# PCB-JOY-4AXIS_adaptorHirose.net
KiCad netlist of a schematic drawn in EAGLE
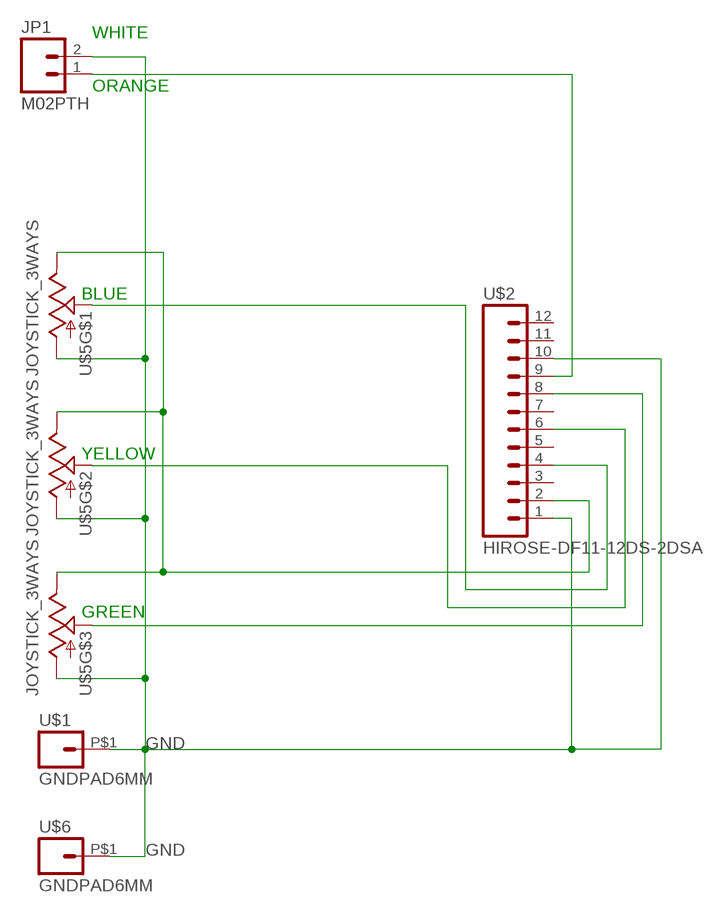
[diagram p0: schematic, sheet 1]

(export (version "E")
  (design (tool "Eeschema 10.0.6"))
  (components
    (comp (ref "JP1")
      (value "M02PTH")
      (footprint "eagle-import:1X02")
      (libsource (lib "eagle-import") (part "M02PTH"))
    )
    (comp (ref "U$1")
      (value "GNDPAD6MM")
      (footprint "eagle-import:3.2MMPAD6MM")
      (libsource (lib "eagle-import") (part "GNDPAD6MM"))
    )
    (comp (ref "U$2")
      (value "HIROSE-DF11-12DS-2DSA")
      (footprint "eagle-import:2X6HIROSE_DF11-12DS-2DSA")
      (libsource (lib "eagle-import") (part "HIROSE-DF11-12DS-2DSA"))
    )
    (comp (ref "U$5")
      (value "JOYSTICK_3WAYS")
      (footprint "eagle-import:JOYSTICK")
      (libsource (lib "eagle-import") (part "JOYSTICK_3WAYS"))
    )
    (comp (ref "U$6")
      (value "GNDPAD6MM")
      (footprint "eagle-import:3.2MMPAD6MM")
      (libsource (lib "eagle-import") (part "GNDPAD6MM"))
    )
  )
  (nets
    (net (code "1") (name "/GND") (class "Default")
      (node (ref "JP1") (pin "2") (pinfunction "2_2") (pintype "passive"))
      (node (ref "U$1") (pin "P$1") (pinfunction "1_P$1") (pintype "passive"))
      (node (ref "U$2") (pin "1") (pinfunction "1_1") (pintype "passive"))
      (node (ref "U$2") (pin "10") (pinfunction "10_10") (pintype "passive"))
      (node (ref "U$5") (pin "LR_COM") (pinfunction "A_LR_COM") (pintype "passive"))
      (node (ref "U$5") (pin "ROT_COM") (pinfunction "A_ROT_COM") (pintype "passive"))
      (node (ref "U$5") (pin "UD_COM") (pinfunction "A_UD_COM") (pintype "passive"))
      (node (ref "U$6") (pin "P$1") (pinfunction "1_P$1") (pintype "passive"))
    )
    (net (code "2") (name "Net-(JP1-Pad1)") (class "Default")
      (node (ref "JP1") (pin "1") (pinfunction "1_1") (pintype "passive"))
      (node (ref "U$2") (pin "9") (pinfunction "9_9") (pintype "passive"))
    )
    (net (code "3") (name "Net-(U$5A-E)") (class "Default")
      (node (ref "U$2") (pin "2") (pinfunction "2_2") (pintype "passive"))
      (node (ref "U$5") (pin "LR_V") (pinfunction "E_LR_V") (pintype "passive"))
      (node (ref "U$5") (pin "ROT_V") (pinfunction "E_ROT_V") (pintype "passive"))
      (node (ref "U$5") (pin "UD_V") (pinfunction "E_UD_V") (pintype "passive"))
    )
    (net (code "4") (name "Net-(U$5A-S)") (class "Default")
      (node (ref "U$2") (pin "4") (pinfunction "4_4") (pintype "passive"))
      (node (ref "U$5") (pin "LR_C") (pinfunction "S_LR_C") (pintype "passive"))
    )
    (net (code "5") (name "Net-(U$5B-S)") (class "Default")
      (node (ref "U$2") (pin "6") (pinfunction "6_6") (pintype "passive"))
      (node (ref "U$5") (pin "UD_C") (pinfunction "S_UD_C") (pintype "passive"))
    )
    (net (code "6") (name "Net-(U$5C-S)") (class "Default")
      (node (ref "U$2") (pin "8") (pinfunction "8_8") (pintype "passive"))
      (node (ref "U$5") (pin "ROT_C") (pinfunction "S_ROT_C") (pintype "passive"))
    )
    (net (code "7") (name "unconnected-(U$2-Pad3)") (class "Default")
      (node (ref "U$2") (pin "3") (pinfunction "3_3") (pintype "passive"))
    )
    (net (code "8") (name "unconnected-(U$2-Pad5)") (class "Default")
      (node (ref "U$2") (pin "5") (pinfunction "5_5") (pintype "passive"))
    )
    (net (code "9") (name "unconnected-(U$2-Pad7)") (class "Default")
      (node (ref "U$2") (pin "7") (pinfunction "7_7") (pintype "passive"))
    )
    (net (code "10") (name "unconnected-(U$2-Pad11)") (class "Default")
      (node (ref "U$2") (pin "11") (pinfunction "11_11") (pintype "passive"))
    )
    (net (code "11") (name "unconnected-(U$2-Pad12)") (class "Default")
      (node (ref "U$2") (pin "12") (pinfunction "12_12") (pintype "passive"))
    )
  )
)
